# DDS.net
KiCad netlist of a schematic drawn in Altium Designer
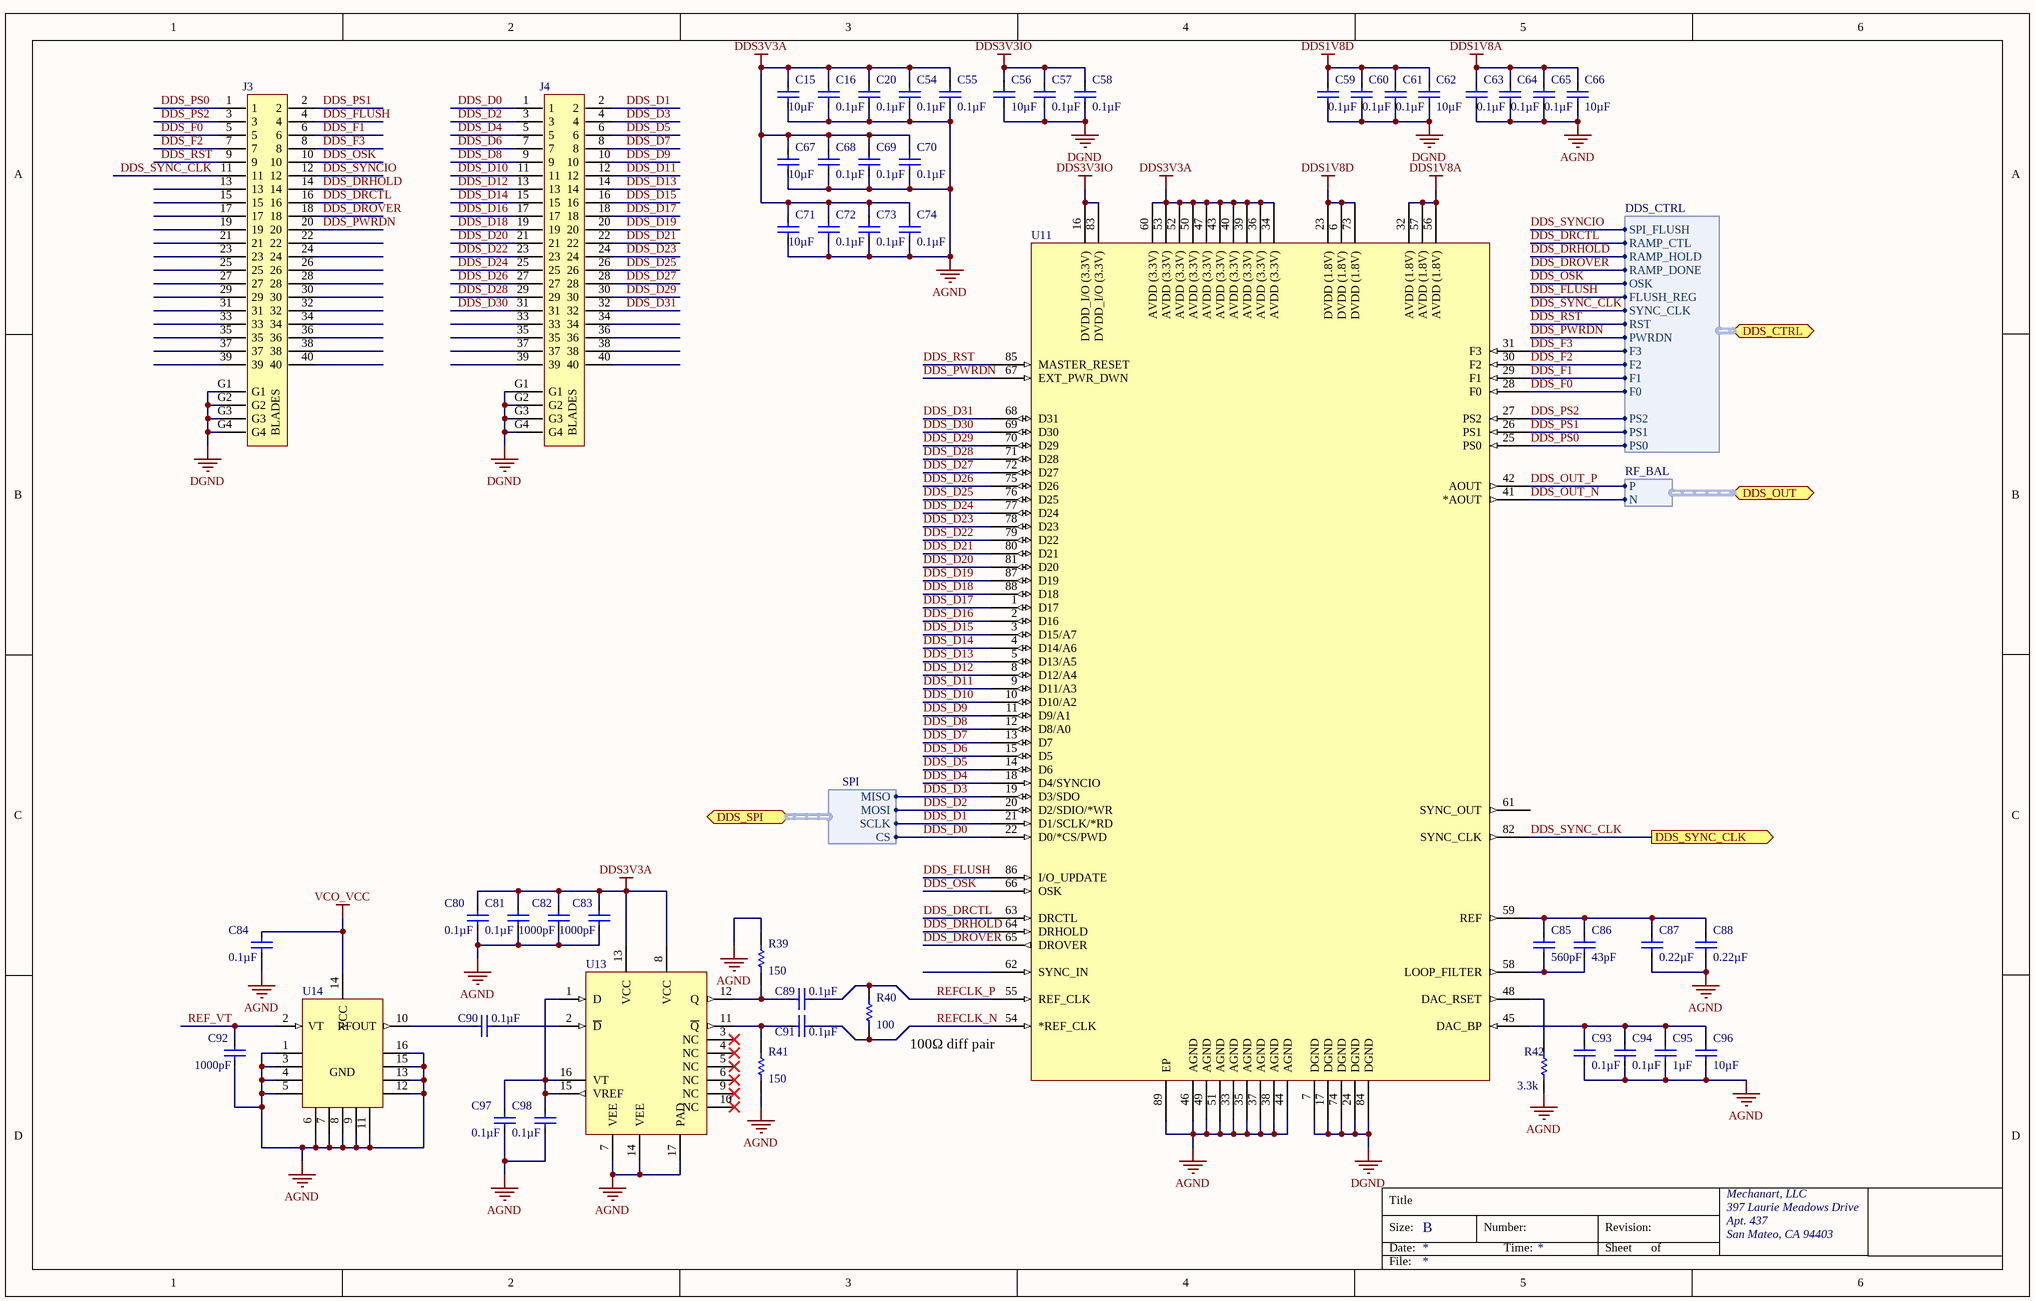
[diagram p0: DDS.SchDoc]

(export (version "E")
  (design (tool "Eeschema 10.0.6"))
  (components
    (comp (ref "C15")
      (value "10µF")
      (footprint "CAPC1608X85L22N")
      (description "CAP CER 10UF 25V X7R 1206")
      (fields
        (field (name "MANUFACTURER") "Murata Electronics North America")
        (field (name "MANUFACTURER PART NUMBER") "GRM31CR71E106KA12L")
      )
      (libsource (lib "mechanart_oshw") (part "CapSMT"))
    )
    (comp (ref "C16")
      (value "0.1µF")
      (footprint "CAPC1005X55L25N")
      (description "CAP CER 0.1UF 16V X7R 0402")
      (fields
        (field (name "MANUFACTURER") "Murata Electronics North America")
        (field (name "MANUFACTURER PART NUMBER") "GRM155R71C104JA88D")
      )
      (libsource (lib "mechanart_oshw") (part "CapSMT"))
    )
    (comp (ref "C20")
      (value "0.1µF")
      (footprint "CAPC1005X55L25N")
      (description "CAP CER 0.1UF 16V X7R 0402")
      (fields
        (field (name "MANUFACTURER") "Murata Electronics North America")
        (field (name "MANUFACTURER PART NUMBER") "GRM155R71C104JA88D")
      )
      (libsource (lib "mechanart_oshw") (part "CapSMT"))
    )
    (comp (ref "C54")
      (value "0.1µF")
      (footprint "CAPC1005X55L25N")
      (description "CAP CER 0.1UF 16V X7R 0402")
      (fields
        (field (name "MANUFACTURER") "Murata Electronics North America")
        (field (name "MANUFACTURER PART NUMBER") "GRM155R71C104JA88D")
      )
      (libsource (lib "mechanart_oshw") (part "CapSMT"))
    )
    (comp (ref "C55")
      (value "0.1µF")
      (footprint "CAPC1005X55L25N")
      (description "CAP CER 0.1UF 16V X7R 0402")
      (fields
        (field (name "MANUFACTURER") "Murata Electronics North America")
        (field (name "MANUFACTURER PART NUMBER") "GRM155R71C104JA88D")
      )
      (libsource (lib "mechanart_oshw") (part "CapSMT"))
    )
    (comp (ref "C56")
      (value "10µF")
      (footprint "CAPC1608X85L22N")
      (description "CAP CER 10UF 25V X7R 1206")
      (fields
        (field (name "MANUFACTURER") "Murata Electronics North America")
        (field (name "MANUFACTURER PART NUMBER") "GRM31CR71E106KA12L")
      )
      (libsource (lib "mechanart_oshw") (part "CapSMT"))
    )
    (comp (ref "C57")
      (value "0.1µF")
      (footprint "CAPC1005X55L25N")
      (description "CAP CER 0.1UF 16V X7R 0402")
      (fields
        (field (name "MANUFACTURER") "Murata Electronics North America")
        (field (name "MANUFACTURER PART NUMBER") "GRM155R71C104JA88D")
      )
      (libsource (lib "mechanart_oshw") (part "CapSMT"))
    )
    (comp (ref "C58")
      (value "0.1µF")
      (footprint "CAPC1005X55L25N")
      (description "CAP CER 0.1UF 16V X7R 0402")
      (fields
        (field (name "MANUFACTURER") "Murata Electronics North America")
        (field (name "MANUFACTURER PART NUMBER") "GRM155R71C104JA88D")
      )
      (libsource (lib "mechanart_oshw") (part "CapSMT"))
    )
    (comp (ref "C59")
      (value "0.1µF")
      (footprint "CAPC1005X55L25N")
      (description "CAP CER 0.1UF 16V X7R 0402")
      (fields
        (field (name "MANUFACTURER") "Murata Electronics North America")
        (field (name "MANUFACTURER PART NUMBER") "GRM155R71C104JA88D")
      )
      (libsource (lib "mechanart_oshw") (part "CapSMT"))
    )
    (comp (ref "C60")
      (value "0.1µF")
      (footprint "CAPC1005X55L25N")
      (description "CAP CER 0.1UF 16V X7R 0402")
      (fields
        (field (name "MANUFACTURER") "Murata Electronics North America")
        (field (name "MANUFACTURER PART NUMBER") "GRM155R71C104JA88D")
      )
      (libsource (lib "mechanart_oshw") (part "CapSMT"))
    )
    (comp (ref "C61")
      (value "0.1µF")
      (footprint "CAPC1005X55L25N")
      (description "CAP CER 0.1UF 16V X7R 0402")
      (fields
        (field (name "MANUFACTURER") "Murata Electronics North America")
        (field (name "MANUFACTURER PART NUMBER") "GRM155R71C104JA88D")
      )
      (libsource (lib "mechanart_oshw") (part "CapSMT"))
    )
    (comp (ref "C62")
      (value "10µF")
      (footprint "CAPC1608X85L22N")
      (description "CAP CER 10UF 25V X7R 1206")
      (fields
        (field (name "MANUFACTURER") "Murata Electronics North America")
        (field (name "MANUFACTURER PART NUMBER") "GRM31CR71E106KA12L")
      )
      (libsource (lib "mechanart_oshw") (part "CapSMT"))
    )
    (comp (ref "C63")
      (value "0.1µF")
      (footprint "CAPC1005X55L25N")
      (description "CAP CER 0.1UF 16V X7R 0402")
      (fields
        (field (name "MANUFACTURER") "Murata Electronics North America")
        (field (name "MANUFACTURER PART NUMBER") "GRM155R71C104JA88D")
      )
      (libsource (lib "mechanart_oshw") (part "CapSMT"))
    )
    (comp (ref "C64")
      (value "0.1µF")
      (footprint "CAPC1005X55L25N")
      (description "CAP CER 0.1UF 16V X7R 0402")
      (fields
        (field (name "MANUFACTURER") "Murata Electronics North America")
        (field (name "MANUFACTURER PART NUMBER") "GRM155R71C104JA88D")
      )
      (libsource (lib "mechanart_oshw") (part "CapSMT"))
    )
    (comp (ref "C65")
      (value "0.1µF")
      (footprint "CAPC1005X55L25N")
      (description "CAP CER 0.1UF 16V X7R 0402")
      (fields
        (field (name "MANUFACTURER") "Murata Electronics North America")
        (field (name "MANUFACTURER PART NUMBER") "GRM155R71C104JA88D")
      )
      (libsource (lib "mechanart_oshw") (part "CapSMT"))
    )
    (comp (ref "C66")
      (value "10µF")
      (footprint "CAPC1608X85L22N")
      (description "CAP CER 10UF 25V X7R 1206")
      (fields
        (field (name "MANUFACTURER") "Murata Electronics North America")
        (field (name "MANUFACTURER PART NUMBER") "GRM31CR71E106KA12L")
      )
      (libsource (lib "mechanart_oshw") (part "CapSMT"))
    )
    (comp (ref "C67")
      (value "10µF")
      (footprint "CAPC1608X85L22N")
      (description "CAP CER 10UF 25V X7R 1206")
      (fields
        (field (name "MANUFACTURER") "Murata Electronics North America")
        (field (name "MANUFACTURER PART NUMBER") "GRM31CR71E106KA12L")
      )
      (libsource (lib "mechanart_oshw") (part "CapSMT"))
    )
    (comp (ref "C68")
      (value "0.1µF")
      (footprint "CAPC1005X55L25N")
      (description "CAP CER 0.1UF 16V X7R 0402")
      (fields
        (field (name "MANUFACTURER") "Murata Electronics North America")
        (field (name "MANUFACTURER PART NUMBER") "GRM155R71C104JA88D")
      )
      (libsource (lib "mechanart_oshw") (part "CapSMT"))
    )
    (comp (ref "C69")
      (value "0.1µF")
      (footprint "CAPC1005X55L25N")
      (description "CAP CER 0.1UF 16V X7R 0402")
      (fields
        (field (name "MANUFACTURER") "Murata Electronics North America")
        (field (name "MANUFACTURER PART NUMBER") "GRM155R71C104JA88D")
      )
      (libsource (lib "mechanart_oshw") (part "CapSMT"))
    )
    (comp (ref "C70")
      (value "0.1µF")
      (footprint "CAPC1005X55L25N")
      (description "CAP CER 0.1UF 16V X7R 0402")
      (fields
        (field (name "MANUFACTURER") "Murata Electronics North America")
        (field (name "MANUFACTURER PART NUMBER") "GRM155R71C104JA88D")
      )
      (libsource (lib "mechanart_oshw") (part "CapSMT"))
    )
    (comp (ref "C71")
      (value "10µF")
      (footprint "CAPC1608X85L22N")
      (description "CAP CER 10UF 25V X7R 1206")
      (fields
        (field (name "MANUFACTURER") "Murata Electronics North America")
        (field (name "MANUFACTURER PART NUMBER") "GRM31CR71E106KA12L")
      )
      (libsource (lib "mechanart_oshw") (part "CapSMT"))
    )
    (comp (ref "C72")
      (value "0.1µF")
      (footprint "CAPC1005X55L25N")
      (description "CAP CER 0.1UF 16V X7R 0402")
      (fields
        (field (name "MANUFACTURER") "Murata Electronics North America")
        (field (name "MANUFACTURER PART NUMBER") "GRM155R71C104JA88D")
      )
      (libsource (lib "mechanart_oshw") (part "CapSMT"))
    )
    (comp (ref "C73")
      (value "0.1µF")
      (footprint "CAPC1005X55L25N")
      (description "CAP CER 0.1UF 16V X7R 0402")
      (fields
        (field (name "MANUFACTURER") "Murata Electronics North America")
        (field (name "MANUFACTURER PART NUMBER") "GRM155R71C104JA88D")
      )
      (libsource (lib "mechanart_oshw") (part "CapSMT"))
    )
    (comp (ref "C74")
      (value "0.1µF")
      (footprint "CAPC1005X55L25N")
      (description "CAP CER 0.1UF 16V X7R 0402")
      (fields
        (field (name "MANUFACTURER") "Murata Electronics North America")
        (field (name "MANUFACTURER PART NUMBER") "GRM155R71C104JA88D")
      )
      (libsource (lib "mechanart_oshw") (part "CapSMT"))
    )
    (comp (ref "C80")
      (value "0.1µF")
      (footprint "CAPC1005X50L25N")
      (description "CAP CER 0.1UF 50V X7R 0402")
      (fields
        (field (name "MANUFACTURER") "Murata Electronics North America")
        (field (name "MANUFACTURER PART NUMBER") "GRM155R71H104KE14D")
      )
      (libsource (lib "mechanart_oshw") (part "CapSMT"))
    )
    (comp (ref "C81")
      (value "0.1µF")
      (footprint "CAPC1005X50L25N")
      (description "CAP CER 0.1UF 50V X7R 0402")
      (fields
        (field (name "MANUFACTURER") "Murata Electronics North America")
        (field (name "MANUFACTURER PART NUMBER") "GRM155R71H104KE14D")
      )
      (libsource (lib "mechanart_oshw") (part "CapSMT"))
    )
    (comp (ref "C82")
      (value "1000pF")
      (footprint "CAPC1005X50L25N")
      (description "CAP CER 1000PF 50V NP0 0402")
      (fields
        (field (name "MANUFACTURER") "Murata Electronics North America")
        (field (name "MANUFACTURER PART NUMBER") "GRM1555C1H102JA01D")
      )
      (libsource (lib "mechanart_oshw") (part "CapSMT"))
    )
    (comp (ref "C83")
      (value "1000pF")
      (footprint "CAPC1005X50L25N")
      (description "CAP CER 1000PF 50V NP0 0402")
      (fields
        (field (name "MANUFACTURER") "Murata Electronics North America")
        (field (name "MANUFACTURER PART NUMBER") "GRM1555C1H102JA01D")
      )
      (libsource (lib "mechanart_oshw") (part "CapSMT"))
    )
    (comp (ref "C84")
      (value "0.1µF")
      (footprint "CAPC1005X50L25N")
      (description "CAP CER 0.1UF 50V X7R 0402")
      (fields
        (field (name "MANUFACTURER") "Murata Electronics North America")
        (field (name "MANUFACTURER PART NUMBER") "GRM155R71H104KE14D")
      )
      (libsource (lib "mechanart_oshw") (part "CapSMT"))
    )
    (comp (ref "C85")
      (value "560pF")
      (footprint "CAPC1005X50L25N")
      (description "CAP CER 560PF 50V NP0 0402")
      (fields
        (field (name "MANUFACTURER") "Murata Electronics North America")
        (field (name "MANUFACTURER PART NUMBER") "GRM1555C1H561JA01D")
      )
      (libsource (lib "mechanart_oshw") (part "CapSMT"))
    )
    (comp (ref "C86")
      (value "43pF")
      (footprint "CAPC1005X50L25N")
      (description "CAP CER 43PF 50V NP0 0402")
      (fields
        (field (name "MANUFACTURER") "Murata Electronics North America")
        (field (name "MANUFACTURER PART NUMBER") "GRM1555C1H430JA01D")
      )
      (libsource (lib "mechanart_oshw") (part "CapSMT"))
    )
    (comp (ref "C87")
      (value "0.22µF")
      (footprint "CAPC1005X50L25N")
      (description "CAP CER 0.22UF 35V 10% X5R 0402")
      (fields
        (field (name "MANUFACTURER") "Murata Electronics North America")
        (field (name "MANUFACTURER PART NUMBER") "GRT155R6YA224KE01D")
      )
      (libsource (lib "mechanart_oshw") (part "CapSMT"))
    )
    (comp (ref "C88")
      (value "0.22µF")
      (footprint "CAPC1005X50L25N")
      (description "CAP CER 0.22UF 35V 10% X5R 0402")
      (fields
        (field (name "MANUFACTURER") "Murata Electronics North America")
        (field (name "MANUFACTURER PART NUMBER") "GRT155R6YA224KE01D")
      )
      (libsource (lib "mechanart_oshw") (part "CapSMT"))
    )
    (comp (ref "C89")
      (value "0.1µF")
      (footprint "CAPC1005X55L25N")
      (description "CAP CER 0.1UF 16V X7R 0402")
      (fields
        (field (name "MANUFACTURER") "Murata Electronics North America")
        (field (name "MANUFACTURER PART NUMBER") "GRM155R71C104JA88D")
      )
      (libsource (lib "mechanart_oshw") (part "CapSMT"))
    )
    (comp (ref "C90")
      (value "0.1µF")
      (footprint "CAPC1005X55L25N")
      (description "CAP CER 0.1UF 16V X7R 0402")
      (fields
        (field (name "MANUFACTURER") "Murata Electronics North America")
        (field (name "MANUFACTURER PART NUMBER") "GRM155R71C104JA88D")
      )
      (libsource (lib "mechanart_oshw") (part "CapSMT"))
    )
    (comp (ref "C91")
      (value "0.1µF")
      (footprint "CAPC1005X55L25N")
      (description "CAP CER 0.1UF 16V X7R 0402")
      (fields
        (field (name "MANUFACTURER") "Murata Electronics North America")
        (field (name "MANUFACTURER PART NUMBER") "GRM155R71C104JA88D")
      )
      (libsource (lib "mechanart_oshw") (part "CapSMT"))
    )
    (comp (ref "C92")
      (value "1000pF")
      (footprint "CAPC1005X50L25N")
      (description "CAP CER 1000PF 50V NP0 0402")
      (fields
        (field (name "MANUFACTURER") "Murata Electronics North America")
        (field (name "MANUFACTURER PART NUMBER") "GRM1555C1H102JA01D")
      )
      (libsource (lib "mechanart_oshw") (part "CapSMT"))
    )
    (comp (ref "C93")
      (value "0.1µF")
      (footprint "CAPC1005X55L25N")
      (description "CAP CER 0.1UF 16V X7R 0402")
      (fields
        (field (name "MANUFACTURER") "Murata Electronics North America")
        (field (name "MANUFACTURER PART NUMBER") "GRM155R71C104JA88D")
      )
      (libsource (lib "mechanart_oshw") (part "CapSMT"))
    )
    (comp (ref "C94")
      (value "0.1µF")
      (footprint "CAPC1005X55L25N")
      (description "CAP CER 0.1UF 16V X7R 0402")
      (fields
        (field (name "MANUFACTURER") "Murata Electronics North America")
        (field (name "MANUFACTURER PART NUMBER") "GRM155R71C104JA88D")
      )
      (libsource (lib "mechanart_oshw") (part "CapSMT"))
    )
    (comp (ref "C95")
      (value "1µF")
      (footprint "CAPC1608X85L22N")
      (description "CAP CER 1UF 16V X7R 0603")
      (fields
        (field (name "MANUFACTURER") "Taiyo Yuden")
        (field (name "MANUFACTURER PART NUMBER") "EMK107B7105KA-T")
      )
      (libsource (lib "mechanart_oshw") (part "CapSMT"))
    )
    (comp (ref "C96")
      (value "10µF")
      (footprint "CAPC1608X85L22N")
      (description "CAP CER 10UF 25V X7R 1206")
      (fields
        (field (name "MANUFACTURER") "Murata Electronics North America")
        (field (name "MANUFACTURER PART NUMBER") "GRM31CR71E106KA12L")
      )
      (libsource (lib "mechanart_oshw") (part "CapSMT"))
    )
    (comp (ref "C97")
      (value "0.1µF")
      (footprint "CAPC1005X50L25N")
      (description "CAP CER 0.1UF 50V X7R 0402")
      (fields
        (field (name "MANUFACTURER") "Murata Electronics North America")
        (field (name "MANUFACTURER PART NUMBER") "GRM155R71H104KE14D")
      )
      (libsource (lib "mechanart_oshw") (part "CapSMT"))
    )
    (comp (ref "C98")
      (value "0.1µF")
      (footprint "CAPC1005X50L25N")
      (description "CAP CER 0.1UF 50V X7R 0402")
      (fields
        (field (name "MANUFACTURER") "Murata Electronics North America")
        (field (name "MANUFACTURER PART NUMBER") "GRM155R71H104KE14D")
      )
      (libsource (lib "mechanart_oshw") (part "CapSMT"))
    )
    (comp (ref "J3")
      (value "QSE-020-01-X-D-A")
      (footprint "QSE-020-01-X-D-A")
      (description "CONN RCPT HI-SPEED DUAL 40POS")
      (fields
        (field (name "MANUFACTURER") "Samtec Inc.")
        (field (name "MANUFACTURER PART NUMBER") "QSE-020-01-L-D-A")
      )
      (libsource (lib "mechanart_oshw") (part "QSE-020-01-X-D-A"))
    )
    (comp (ref "J4")
      (value "QSE-020-01-X-D-A")
      (footprint "QSE-020-01-X-D-A")
      (description "CONN RCPT HI-SPEED DUAL 40POS")
      (fields
        (field (name "MANUFACTURER") "Samtec Inc.")
        (field (name "MANUFACTURER PART NUMBER") "QSE-020-01-L-D-A")
      )
      (libsource (lib "mechanart_oshw") (part "QSE-020-01-X-D-A"))
    )
    (comp (ref "R39")
      (value "150")
      (footprint "RESC1005X40L25N")
      (description "RES SMD 150 OHM 1% 1/10W 0402")
      (fields
        (field (name "MANUFACTURER") "Panasonic Electronic Components")
        (field (name "MANUFACTURER PART NUMBER") "ERJ-2RKF1500X")
      )
      (libsource (lib "mechanart_oshw") (part "ResSMT"))
    )
    (comp (ref "R40")
      (value "100")
      (footprint "RESC1005X40L25N")
      (description "RES SMD 100 OHM 1% 1/10W 0402")
      (fields
        (field (name "MANUFACTURER") "Panasonic Electronic Components")
        (field (name "MANUFACTURER PART NUMBER") "ERJ-2RKF1000X")
      )
      (libsource (lib "mechanart_oshw") (part "ResSMT"))
    )
    (comp (ref "R41")
      (value "150")
      (footprint "RESC1005X40L25N")
      (description "RES SMD 150 OHM 1% 1/10W 0402")
      (fields
        (field (name "MANUFACTURER") "Panasonic Electronic Components")
        (field (name "MANUFACTURER PART NUMBER") "ERJ-2RKF1500X")
      )
      (libsource (lib "mechanart_oshw") (part "ResSMT"))
    )
    (comp (ref "R42")
      (value "3.3k")
      (footprint "RESC1005X40L25N")
      (description "RES SMD 3.3K OHM 1% 1/10W 0402")
      (fields
        (field (name "MANUFACTURER") "Panasonic Electronic Components")
        (field (name "MANUFACTURER PART NUMBER") "ERJ-2RKF3301X")
      )
      (libsource (lib "mechanart_oshw") (part "ResSMT"))
    )
    (comp (ref "U11")
      (value "AD9914BCPZ")
      (footprint "QFN50P1200X1200X90-89T670X670N")
      (description "IC DDS 3.5GSPS DAC 12BIT 88LFCSP")
      (fields (field (name "MANUFACTURER") "Analog Devices Inc"))
      (libsource (lib "mechanart_oshw") (part "AD9914BCPZ"))
    )
    (comp (ref "U13")
      (value "ADCLK905")
      (footprint "QFN50P300X300X90-17T150X150N")
      (description "IC CLK BUFFER 1:1 7.5GHZ 16LFCSP")
      (fields
        (field (name "MANUFACTURER") "Analog Devices Inc.")
        (field (name "MANUFACTURER PART NUMBER") "ADCLK905BCPZ-R7")
      )
      (libsource (lib "mechanart_oshw") (part "ADCLK905"))
    )
    (comp (ref "U14")
      (value "CVCO55")
      (footprint "CVCO55")
      (description "OSC CRO 3500-3700 MHZ SMD .5X.5\"")
      (fields
        (field (name "MANUFACTURER") "Crystek Corporation")
        (field (name "MANUFACTURER PART NUMBER") "CVCO55CC-3500-3700")
      )
      (libsource (lib "mechanart_oshw") (part "CVCO55"))
    )
  )
  (nets
    (net (code "4") (name "/DDS_D0") (class "Default")
      (node (ref "J4") (pin "1") (pinfunction "1_1") (pintype "passive"))
      (node (ref "U11") (pin "22") (pinfunction "D0/*CS/PWD_22") (pintype "input"))
    )
    (net (code "5") (name "/DDS_D1") (class "Default")
      (node (ref "J4") (pin "2") (pinfunction "2_2") (pintype "passive"))
      (node (ref "U11") (pin "21") (pinfunction "D1/SCLK/*RD_21") (pintype "input"))
    )
    (net (code "6") (name "/DDS_D2") (class "Default")
      (node (ref "J4") (pin "3") (pinfunction "3_3") (pintype "passive"))
      (node (ref "U11") (pin "20") (pinfunction "D2/SDIO/*WR_20") (pintype "bidirectional"))
    )
    (net (code "7") (name "/DDS_D3") (class "Default")
      (node (ref "J4") (pin "4") (pinfunction "4_4") (pintype "passive"))
      (node (ref "U11") (pin "19") (pinfunction "D3/SDO_19") (pintype "bidirectional"))
    )
    (net (code "8") (name "/DDS_D4") (class "Default")
      (node (ref "J4") (pin "5") (pinfunction "5_5") (pintype "passive"))
      (node (ref "U11") (pin "18") (pinfunction "D4/SYNCIO_18") (pintype "input"))
    )
    (net (code "9") (name "/DDS_D5") (class "Default")
      (node (ref "J4") (pin "6") (pinfunction "6_6") (pintype "passive"))
      (node (ref "U11") (pin "14") (pinfunction "D6_14") (pintype "bidirectional"))
    )
    (net (code "10") (name "/DDS_D6") (class "Default")
      (node (ref "J4") (pin "7") (pinfunction "7_7") (pintype "passive"))
      (node (ref "U11") (pin "15") (pinfunction "D5_15") (pintype "bidirectional"))
    )
    (net (code "11") (name "/DDS_D7") (class "Default")
      (node (ref "J4") (pin "8") (pinfunction "8_8") (pintype "passive"))
      (node (ref "U11") (pin "13") (pinfunction "D7_13") (pintype "bidirectional"))
    )
    (net (code "12") (name "/DDS_D8") (class "Default")
      (node (ref "J4") (pin "9") (pinfunction "9_9") (pintype "passive"))
      (node (ref "U11") (pin "12") (pinfunction "D8/A0_12") (pintype "bidirectional"))
    )
    (net (code "13") (name "/DDS_D9") (class "Default")
      (node (ref "J4") (pin "10") (pinfunction "10_10") (pintype "passive"))
      (node (ref "U11") (pin "11") (pinfunction "D9/A1_11") (pintype "bidirectional"))
    )
    (net (code "14") (name "/DDS_D10") (class "Default")
      (node (ref "J4") (pin "11") (pinfunction "11_11") (pintype "passive"))
      (node (ref "U11") (pin "10") (pinfunction "D10/A2_10") (pintype "bidirectional"))
    )
    (net (code "15") (name "/DDS_D11") (class "Default")
      (node (ref "J4") (pin "12") (pinfunction "12_12") (pintype "passive"))
      (node (ref "U11") (pin "9") (pinfunction "D11/A3_9") (pintype "bidirectional"))
    )
    (net (code "16") (name "/DDS_D12") (class "Default")
      (node (ref "J4") (pin "13") (pinfunction "13_13") (pintype "passive"))
      (node (ref "U11") (pin "8") (pinfunction "D12/A4_8") (pintype "bidirectional"))
    )
    (net (code "17") (name "/DDS_D13") (class "Default")
      (node (ref "J4") (pin "14") (pinfunction "14_14") (pintype "passive"))
      (node (ref "U11") (pin "5") (pinfunction "D13/A5_5") (pintype "bidirectional"))
    )
    (net (code "18") (name "/DDS_D14") (class "Default")
      (node (ref "J4") (pin "15") (pinfunction "15_15") (pintype "passive"))
      (node (ref "U11") (pin "4") (pinfunction "D14/A6_4") (pintype "bidirectional"))
    )
    (net (code "19") (name "/DDS_D15") (class "Default")
      (node (ref "J4") (pin "16") (pinfunction "16_16") (pintype "passive"))
      (node (ref "U11") (pin "3") (pinfunction "D15/A7_3") (pintype "bidirectional"))
    )
    (net (code "20") (name "/DDS_D16") (class "Default")
      (node (ref "J4") (pin "17") (pinfunction "17_17") (pintype "passive"))
      (node (ref "U11") (pin "2") (pinfunction "D16_2") (pintype "bidirectional"))
    )
    (net (code "21") (name "/DDS_D17") (class "Default")
      (node (ref "J4") (pin "18") (pinfunction "18_18") (pintype "passive"))
      (node (ref "U11") (pin "1") (pinfunction "D17_1") (pintype "bidirectional"))
    )
    (net (code "22") (name "/DDS_D18") (class "Default")
      (node (ref "J4") (pin "19") (pinfunction "19_19") (pintype "passive"))
      (node (ref "U11") (pin "88") (pinfunction "D18_88") (pintype "bidirectional"))
    )
    (net (code "23") (name "/DDS_D19") (class "Default")
      (node (ref "J4") (pin "20") (pinfunction "20_20") (pintype "passive"))
      (node (ref "U11") (pin "87") (pinfunction "D19_87") (pintype "bidirectional"))
    )
    (net (code "24") (name "/DDS_D20") (class "Default")
      (node (ref "J4") (pin "21") (pinfunction "21_21") (pintype "passive"))
      (node (ref "U11") (pin "81") (pinfunction "D20_81") (pintype "bidirectional"))
    )
    (net (code "25") (name "/DDS_D21") (class "Default")
      (node (ref "J4") (pin "22") (pinfunction "22_22") (pintype "passive"))
      (node (ref "U11") (pin "80") (pinfunction "D21_80") (pintype "bidirectional"))
    )
    (net (code "26") (name "/DDS_D22") (class "Default")
      (node (ref "J4") (pin "23") (pinfunction "23_23") (pintype "passive"))
      (node (ref "U11") (pin "79") (pinfunction "D22_79") (pintype "bidirectional"))
    )
    (net (code "27") (name "/DDS_D23") (class "Default")
      (node (ref "J4") (pin "24") (pinfunction "24_24") (pintype "passive"))
      (node (ref "U11") (pin "78") (pinfunction "D23_78") (pintype "bidirectional"))
    )
    (net (code "28") (name "/DDS_D24") (class "Default")
      (node (ref "J4") (pin "25") (pinfunction "25_25") (pintype "passive"))
      (node (ref "U11") (pin "77") (pinfunction "D24_77") (pintype "bidirectional"))
    )
    (net (code "29") (name "/DDS_D25") (class "Default")
      (node (ref "J4") (pin "26") (pinfunction "26_26") (pintype "passive"))
      (node (ref "U11") (pin "76") (pinfunction "D25_76") (pintype "bidirectional"))
    )
    (net (code "30") (name "/DDS_D26") (class "Default")
      (node (ref "J4") (pin "27") (pinfunction "27_27") (pintype "passive"))
      (node (ref "U11") (pin "75") (pinfunction "D26_75") (pintype "bidirectional"))
    )
    (net (code "31") (name "/DDS_D27") (class "Default")
      (node (ref "J4") (pin "28") (pinfunction "28_28") (pintype "passive"))
      (node (ref "U11") (pin "72") (pinfunction "D27_72") (pintype "bidirectional"))
    )
    (net (code "32") (name "/DDS_D28") (class "Default")
      (node (ref "J4") (pin "29") (pinfunction "29_29") (pintype "passive"))
      (node (ref "U11") (pin "71") (pinfunction "D28_71") (pintype "bidirectional"))
    )
    (net (code "33") (name "/DDS_D29") (class "Default")
      (node (ref "J4") (pin "30") (pinfunction "30_30") (pintype "passive"))
      (node (ref "U11") (pin "70") (pinfunction "D29_70") (pintype "bidirectional"))
    )
    (net (code "34") (name "/DDS_D30") (class "Default")
      (node (ref "J4") (pin "31") (pinfunction "31_31") (pintype "passive"))
      (node (ref "U11") (pin "69") (pinfunction "D30_69") (pintype "bidirectional"))
    )
    (net (code "35") (name "/DDS_D31") (class "Default")
      (node (ref "J4") (pin "32") (pinfunction "32_32") (pintype "passive"))
      (node (ref "U11") (pin "68") (pinfunction "D31_68") (pintype "bidirectional"))
    )
    (net (code "36") (name "/DDS_DRCTL") (class "Default")
      (node (ref "J3") (pin "16") (pinfunction "16_16") (pintype "passive"))
      (node (ref "U11") (pin "63") (pinfunction "DRCTL_63") (pintype "input"))
    )
    (net (code "37") (name "/DDS_DRHOLD") (class "Default")
      (node (ref "J3") (pin "14") (pinfunction "14_14") (pintype "passive"))
      (node (ref "U11") (pin "64") (pinfunction "DRHOLD_64") (pintype "input"))
    )
    (net (code "38") (name "/DDS_DROVER") (class "Default")
      (node (ref "J3") (pin "18") (pinfunction "18_18") (pintype "passive"))
      (node (ref "U11") (pin "65") (pinfunction "DROVER_65") (pintype "output"))
    )
    (net (code "39") (name "/DDS_F0") (class "Default")
      (node (ref "J3") (pin "5") (pinfunction "5_5") (pintype "passive"))
      (node (ref "U11") (pin "28") (pinfunction "F0_28") (pintype "input"))
    )
    (net (code "40") (name "/DDS_F1") (class "Default")
      (node (ref "J3") (pin "6") (pinfunction "6_6") (pintype "passive"))
      (node (ref "U11") (pin "29") (pinfunction "F1_29") (pintype "input"))
    )
    (net (code "41") (name "/DDS_F2") (class "Default")
      (node (ref "J3") (pin "7") (pinfunction "7_7") (pintype "passive"))
      (node (ref "U11") (pin "30") (pinfunction "F2_30") (pintype "input"))
    )
    (net (code "42") (name "/DDS_F3") (class "Default")
      (node (ref "J3") (pin "8") (pinfunction "8_8") (pintype "passive"))
      (node (ref "U11") (pin "31") (pinfunction "F3_31") (pintype "input"))
    )
    (net (code "43") (name "/DDS_FLUSH") (class "Default")
      (node (ref "J3") (pin "4") (pinfunction "4_4") (pintype "passive"))
      (node (ref "U11") (pin "86") (pinfunction "I/O_UPDATE_86") (pintype "input"))
    )
    (net (code "44") (name "/DDS_OSK") (class "Default")
      (node (ref "J3") (pin "10") (pinfunction "10_10") (pintype "passive"))
      (node (ref "U11") (pin "66") (pinfunction "OSK_66") (pintype "input"))
    )
    (net (code "45") (name "/DDS_OUT_N") (class "Default")
      (node (ref "U11") (pin "41") (pinfunction "*AOUT_41") (pintype "output"))
    )
    (net (code "46") (name "/DDS_OUT_P") (class "Default")
      (node (ref "U11") (pin "42") (pinfunction "AOUT_42") (pintype "output"))
    )
    (net (code "47") (name "/DDS_PS0") (class "Default")
      (node (ref "J3") (pin "1") (pinfunction "1_1") (pintype "passive"))
      (node (ref "U11") (pin "25") (pinfunction "PS0_25") (pintype "input"))
    )
    (net (code "48") (name "/DDS_PS1") (class "Default")
      (node (ref "J3") (pin "2") (pinfunction "2_2") (pintype "passive"))
      (node (ref "U11") (pin "26") (pinfunction "PS1_26") (pintype "input"))
    )
    (net (code "49") (name "/DDS_PS2") (class "Default")
      (node (ref "J3") (pin "3") (pinfunction "3_3") (pintype "passive"))
      (node (ref "U11") (pin "27") (pinfunction "PS2_27") (pintype "input"))
    )
    (net (code "50") (name "/DDS_PWRDN") (class "Default")
      (node (ref "J3") (pin "20") (pinfunction "20_20") (pintype "passive"))
      (node (ref "U11") (pin "67") (pinfunction "EXT_PWR_DWN_67") (pintype "input"))
    )
    (net (code "51") (name "/DDS_RST") (class "Default")
      (node (ref "J3") (pin "9") (pinfunction "9_9") (pintype "passive"))
      (node (ref "U11") (pin "85") (pinfunction "MASTER_RESET_85") (pintype "input"))
    )
    (net (code "52") (name "/DDS_SYNCIO") (class "Default")
      (node (ref "J3") (pin "12") (pinfunction "12_12") (pintype "passive"))
    )
    (net (code "53") (name "/DDS_SYNC_CLK") (class "Default")
      (node (ref "J3") (pin "11") (pinfunction "11_11") (pintype "passive"))
      (node (ref "U11") (pin "82") (pinfunction "SYNC_CLK_82") (pintype "output"))
    )
    (net (code "54") (name "/REFCLK_N") (class "Default")
      (node (ref "C91") (pin "2") (pinfunction "2_2") (pintype "passive"))
      (node (ref "R40") (pin "1") (pinfunction "1_1") (pintype "passive"))
      (node (ref "U11") (pin "54") (pinfunction "*REF_CLK_54") (pintype "input"))
    )
    (net (code "55") (name "/REFCLK_P") (class "Default")
      (node (ref "C89") (pin "2") (pinfunction "2_2") (pintype "passive"))
      (node (ref "R40") (pin "2") (pinfunction "2_2") (pintype "passive"))
      (node (ref "U11") (pin "55") (pinfunction "REF_CLK_55") (pintype "input"))
    )
    (net (code "56") (name "/REF_VT") (class "Default")
      (node (ref "C92") (pin "1") (pinfunction "1_1") (pintype "passive"))
      (node (ref "U14") (pin "2") (pinfunction "VT_2") (pintype "input"))
    )
    (net (code "60") (name "AGND") (class "Default")
      (node (ref "C15") (pin "2") (pinfunction "2_2") (pintype "passive"))
      (node (ref "C16") (pin "2") (pinfunction "2_2") (pintype "passive"))
      (node (ref "C20") (pin "2") (pinfunction "2_2") (pintype "passive"))
      (node (ref "C54") (pin "2") (pinfunction "2_2") (pintype "passive"))
      (node (ref "C55") (pin "2") (pinfunction "2_2") (pintype "passive"))
      (node (ref "C63") (pin "2") (pinfunction "2_2") (pintype "passive"))
      (node (ref "C64") (pin "2") (pinfunction "2_2") (pintype "passive"))
      (node (ref "C65") (pin "2") (pinfunction "2_2") (pintype "passive"))
      (node (ref "C66") (pin "2") (pinfunction "2_2") (pintype "passive"))
      (node (ref "C67") (pin "2") (pinfunction "2_2") (pintype "passive"))
      (node (ref "C68") (pin "2") (pinfunction "2_2") (pintype "passive"))
      (node (ref "C69") (pin "2") (pinfunction "2_2") (pintype "passive"))
      (node (ref "C70") (pin "2") (pinfunction "2_2") (pintype "passive"))
      (node (ref "C71") (pin "2") (pinfunction "2_2") (pintype "passive"))
      (node (ref "C72") (pin "2") (pinfunction "2_2") (pintype "passive"))
      (node (ref "C73") (pin "2") (pinfunction "2_2") (pintype "passive"))
      (node (ref "C74") (pin "2") (pinfunction "2_2") (pintype "passive"))
      (node (ref "C80") (pin "2") (pinfunction "2_2") (pintype "passive"))
      (node (ref "C81") (pin "2") (pinfunction "2_2") (pintype "passive"))
      (node (ref "C82") (pin "2") (pinfunction "2_2") (pintype "passive"))
      (node (ref "C83") (pin "2") (pinfunction "2_2") (pintype "passive"))
      (node (ref "C84") (pin "2") (pinfunction "2_2") (pintype "passive"))
      (node (ref "C87") (pin "2") (pinfunction "2_2") (pintype "passive"))
      (node (ref "C88") (pin "2") (pinfunction "2_2") (pintype "passive"))
      (node (ref "C92") (pin "2") (pinfunction "2_2") (pintype "passive"))
      (node (ref "C93") (pin "2") (pinfunction "2_2") (pintype "passive"))
      (node (ref "C94") (pin "2") (pinfunction "2_2") (pintype "passive"))
      (node (ref "C95") (pin "2") (pinfunction "2_2") (pintype "passive"))
      (node (ref "C96") (pin "2") (pinfunction "2_2") (pintype "passive"))
      (node (ref "C97") (pin "2") (pinfunction "2_2") (pintype "passive"))
      (node (ref "C98") (pin "2") (pinfunction "2_2") (pintype "passive"))
      (node (ref "R39") (pin "2") (pinfunction "2_2") (pintype "passive"))
      (node (ref "R41") (pin "1") (pinfunction "1_1") (pintype "passive"))
      (node (ref "R42") (pin "1") (pinfunction "1_1") (pintype "passive"))
      (node (ref "U11") (pin "33") (pinfunction "AGND_33") (pintype "power_in"))
      (node (ref "U11") (pin "35") (pinfunction "AGND_35") (pintype "power_in"))
      (node (ref "U11") (pin "37") (pinfunction "AGND_37") (pintype "power_in"))
      (node (ref "U11") (pin "38") (pinfunction "AGND_38") (pintype "power_in"))
      (node (ref "U11") (pin "44") (pinfunction "AGND_44") (pintype "power_in"))
      (node (ref "U11") (pin "46") (pinfunction "AGND_46") (pintype "power_in"))
      (node (ref "U11") (pin "49") (pinfunction "AGND_49") (pintype "power_in"))
      (node (ref "U11") (pin "51") (pinfunction "AGND_51") (pintype "power_in"))
      (node (ref "U11") (pin "89") (pinfunction "EP_89") (pintype "power_in"))
      (node (ref "U13") (pin "14") (pinfunction "VEE_14") (pintype "power_in"))
      (node (ref "U13") (pin "17") (pinfunction "PAD_17") (pintype "passive"))
      (node (ref "U13") (pin "7") (pinfunction "VEE_7") (pintype "power_in"))
      (node (ref "U14") (pin "1") (pinfunction "GND_1") (pintype "power_in"))
      (node (ref "U14") (pin "11") (pinfunction "GND_11") (pintype "power_in"))
      (node (ref "U14") (pin "12") (pinfunction "GND_12") (pintype "power_in"))
      (node (ref "U14") (pin "13") (pinfunction "GND_13") (pintype "power_in"))
      (node (ref "U14") (pin "15") (pinfunction "GND_15") (pintype "power_in"))
      (node (ref "U14") (pin "16") (pinfunction "GND_16") (pintype "power_in"))
      (node (ref "U14") (pin "3") (pinfunction "GND_3") (pintype "power_in"))
      (node (ref "U14") (pin "4") (pinfunction "GND_4") (pintype "power_in"))
      (node (ref "U14") (pin "5") (pinfunction "GND_5") (pintype "power_in"))
      (node (ref "U14") (pin "6") (pinfunction "GND_6") (pintype "power_in"))
      (node (ref "U14") (pin "7") (pinfunction "GND_7") (pintype "power_in"))
      (node (ref "U14") (pin "8") (pinfunction "GND_8") (pintype "power_in"))
      (node (ref "U14") (pin "9") (pinfunction "GND_9") (pintype "power_in"))
    )
    (net (code "61") (name "DDS1V8A") (class "Default")
      (node (ref "C63") (pin "1") (pinfunction "1_1") (pintype "passive"))
      (node (ref "C64") (pin "1") (pinfunction "1_1") (pintype "passive"))
      (node (ref "C65") (pin "1") (pinfunction "1_1") (pintype "passive"))
      (node (ref "C66") (pin "1") (pinfunction "1_1") (pintype "passive"))
      (node (ref "U11") (pin "32") (pinfunction "AVDD_(1.8V)_32") (pintype "power_in"))
      (node (ref "U11") (pin "56") (pinfunction "AVDD_(1.8V)_56") (pintype "power_in"))
      (node (ref "U11") (pin "57") (pinfunction "AVDD_(1.8V)_57") (pintype "power_in"))
    )
    (net (code "62") (name "DDS1V8D") (class "Default")
      (node (ref "C59") (pin "1") (pinfunction "1_1") (pintype "passive"))
      (node (ref "C60") (pin "1") (pinfunction "1_1") (pintype "passive"))
      (node (ref "C61") (pin "1") (pinfunction "1_1") (pintype "passive"))
      (node (ref "C62") (pin "1") (pinfunction "1_1") (pintype "passive"))
      (node (ref "U11") (pin "23") (pinfunction "DVDD_(1.8V)_23") (pintype "power_in"))
      (node (ref "U11") (pin "6") (pinfunction "DVDD_(1.8V)_6") (pintype "power_in"))
      (node (ref "U11") (pin "73") (pinfunction "DVDD_(1.8V)_73") (pintype "power_in"))
    )
    (net (code "63") (name "DDS3V3A") (class "Default")
      (node (ref "C15") (pin "1") (pinfunction "1_1") (pintype "passive"))
      (node (ref "C16") (pin "1") (pinfunction "1_1") (pintype "passive"))
      (node (ref "C20") (pin "1") (pinfunction "1_1") (pintype "passive"))
      (node (ref "C54") (pin "1") (pinfunction "1_1") (pintype "passive"))
      (node (ref "C55") (pin "1") (pinfunction "1_1") (pintype "passive"))
      (node (ref "C67") (pin "1") (pinfunction "1_1") (pintype "passive"))
      (node (ref "C68") (pin "1") (pinfunction "1_1") (pintype "passive"))
      (node (ref "C69") (pin "1") (pinfunction "1_1") (pintype "passive"))
      (node (ref "C70") (pin "1") (pinfunction "1_1") (pintype "passive"))
      (node (ref "C71") (pin "1") (pinfunction "1_1") (pintype "passive"))
      (node (ref "C72") (pin "1") (pinfunction "1_1") (pintype "passive"))
      (node (ref "C73") (pin "1") (pinfunction "1_1") (pintype "passive"))
      (node (ref "C74") (pin "1") (pinfunction "1_1") (pintype "passive"))
      (node (ref "C80") (pin "1") (pinfunction "1_1") (pintype "passive"))
      (node (ref "C81") (pin "1") (pinfunction "1_1") (pintype "passive"))
      (node (ref "C82") (pin "1") (pinfunction "1_1") (pintype "passive"))
      (node (ref "C83") (pin "1") (pinfunction "1_1") (pintype "passive"))
      (node (ref "U11") (pin "34") (pinfunction "AVDD_(3.3V)_34") (pintype "power_in"))
      (node (ref "U11") (pin "36") (pinfunction "AVDD_(3.3V)_36") (pintype "power_in"))
      (node (ref "U11") (pin "39") (pinfunction "AVDD_(3.3V)_39") (pintype "power_in"))
      (node (ref "U11") (pin "40") (pinfunction "AVDD_(3.3V)_40") (pintype "power_in"))
      (node (ref "U11") (pin "43") (pinfunction "AVDD_(3.3V)_43") (pintype "power_in"))
      (node (ref "U11") (pin "47") (pinfunction "AVDD_(3.3V)_47") (pintype "power_in"))
      (node (ref "U11") (pin "50") (pinfunction "AVDD_(3.3V)_50") (pintype "power_in"))
      (node (ref "U11") (pin "52") (pinfunction "AVDD_(3.3V)_52") (pintype "power_in"))
      (node (ref "U11") (pin "53") (pinfunction "AVDD_(3.3V)_53") (pintype "power_in"))
      (node (ref "U11") (pin "60") (pinfunction "AVDD_(3.3V)_60") (pintype "power_in"))
      (node (ref "U13") (pin "13") (pinfunction "VCC_13") (pintype "power_in"))
      (node (ref "U13") (pin "8") (pinfunction "VCC_8") (pintype "power_in"))
    )
    (net (code "64") (name "DDS3V3IO") (class "Default")
      (node (ref "C56") (pin "1") (pinfunction "1_1") (pintype "passive"))
      (node (ref "C57") (pin "1") (pinfunction "1_1") (pintype "passive"))
      (node (ref "C58") (pin "1") (pinfunction "1_1") (pintype "passive"))
      (node (ref "U11") (pin "16") (pinfunction "DVDD_I/O_(3.3V)_16") (pintype "power_in"))
      (node (ref "U11") (pin "83") (pinfunction "DVDD_I/O_(3.3V)_83") (pintype "power_in"))
    )
    (net (code "65") (name "DGND") (class "Default")
      (node (ref "C56") (pin "2") (pinfunction "2_2") (pintype "passive"))
      (node (ref "C57") (pin "2") (pinfunction "2_2") (pintype "passive"))
      (node (ref "C58") (pin "2") (pinfunction "2_2") (pintype "passive"))
      (node (ref "C59") (pin "2") (pinfunction "2_2") (pintype "passive"))
      (node (ref "C60") (pin "2") (pinfunction "2_2") (pintype "passive"))
      (node (ref "C61") (pin "2") (pinfunction "2_2") (pintype "passive"))
      (node (ref "C62") (pin "2") (pinfunction "2_2") (pintype "passive"))
      (node (ref "J3") (pin "G1") (pinfunction "G1_G1") (pintype "passive"))
      (node (ref "J3") (pin "G2") (pinfunction "G2_G2") (pintype "passive"))
      (node (ref "J3") (pin "G3") (pinfunction "G3_G3") (pintype "passive"))
      (node (ref "J3") (pin "G4") (pinfunction "G4_G4") (pintype "passive"))
      (node (ref "J4") (pin "G1") (pinfunction "G1_G1") (pintype "passive"))
      (node (ref "J4") (pin "G2") (pinfunction "G2_G2") (pintype "passive"))
      (node (ref "J4") (pin "G3") (pinfunction "G3_G3") (pintype "passive"))
      (node (ref "J4") (pin "G4") (pinfunction "G4_G4") (pintype "passive"))
      (node (ref "U11") (pin "17") (pinfunction "DGND_17") (pintype "power_in"))
      (node (ref "U11") (pin "24") (pinfunction "DGND_24") (pintype "power_in"))
      (node (ref "U11") (pin "7") (pinfunction "DGND_7") (pintype "power_in"))
      (node (ref "U11") (pin "74") (pinfunction "DGND_74") (pintype "power_in"))
      (node (ref "U11") (pin "84") (pinfunction "DGND_84") (pintype "power_in"))
    )
    (net (code "66") (name "Net-(U11-DAC_BP)") (class "Default")
      (node (ref "C93") (pin "1") (pinfunction "1_1") (pintype "passive"))
      (node (ref "C94") (pin "1") (pinfunction "1_1") (pintype "passive"))
      (node (ref "C95") (pin "1") (pinfunction "1_1") (pintype "passive"))
      (node (ref "C96") (pin "1") (pinfunction "1_1") (pintype "passive"))
      (node (ref "U11") (pin "45") (pinfunction "DAC_BP_45") (pintype "input"))
    )
    (net (code "67") (name "Net-(U11-DAC_RSET)") (class "Default")
      (node (ref "R42") (pin "2") (pinfunction "2_2") (pintype "passive"))
      (node (ref "U11") (pin "48") (pinfunction "DAC_RSET_48") (pintype "output"))
    )
    (net (code "68") (name "Net-(U11-LOOP_FILTER)") (class "Default")
      (node (ref "C85") (pin "2") (pinfunction "2_2") (pintype "passive"))
      (node (ref "C86") (pin "2") (pinfunction "2_2") (pintype "passive"))
      (node (ref "U11") (pin "58") (pinfunction "LOOP_FILTER_58") (pintype "output"))
    )
    (net (code "69") (name "Net-(U11-REF)") (class "Default")
      (node (ref "C85") (pin "1") (pinfunction "1_1") (pintype "passive"))
      (node (ref "C86") (pin "1") (pinfunction "1_1") (pintype "passive"))
      (node (ref "C87") (pin "1") (pinfunction "1_1") (pintype "passive"))
      (node (ref "C88") (pin "1") (pinfunction "1_1") (pintype "passive"))
      (node (ref "U11") (pin "59") (pinfunction "REF_59") (pintype "output"))
    )
    (net (code "70") (name "Net-(U13-D)") (class "Default")
      (node (ref "C97") (pin "1") (pinfunction "1_1") (pintype "passive"))
      (node (ref "C98") (pin "1") (pinfunction "1_1") (pintype "passive"))
      (node (ref "U13") (pin "1") (pinfunction "D_1") (pintype "input"))
      (node (ref "U13") (pin "15") (pinfunction "VREF_15") (pintype "output"))
      (node (ref "U13") (pin "16") (pinfunction "VT_16") (pintype "passive"))
    )
    (net (code "71") (name "Net-(U13-Q)") (class "Default")
      (node (ref "C89") (pin "1") (pinfunction "1_1") (pintype "passive"))
      (node (ref "R39") (pin "1") (pinfunction "1_1") (pintype "passive"))
      (node (ref "U13") (pin "12") (pinfunction "Q_12") (pintype "output"))
    )
    (net (code "72") (name "Net-(U13-~{D})") (class "Default")
      (node (ref "C90") (pin "2") (pinfunction "2_2") (pintype "passive"))
      (node (ref "U13") (pin "2") (pinfunction "~{D}_2") (pintype "input"))
    )
    (net (code "73") (name "Net-(U13-~{Q})") (class "Default")
      (node (ref "C91") (pin "1") (pinfunction "1_1") (pintype "passive"))
      (node (ref "R41") (pin "2") (pinfunction "2_2") (pintype "passive"))
      (node (ref "U13") (pin "11") (pinfunction "~{Q}_11") (pintype "output"))
    )
    (net (code "74") (name "Net-(U14-RFOUT)") (class "Default")
      (node (ref "C90") (pin "1") (pinfunction "1_1") (pintype "passive"))
      (node (ref "U14") (pin "10") (pinfunction "RFOUT_10") (pintype "output"))
    )
    (net (code "75") (name "VCO_VCC") (class "Default")
      (node (ref "C84") (pin "1") (pinfunction "1_1") (pintype "passive"))
      (node (ref "U14") (pin "14") (pinfunction "VCC_14") (pintype "power_in"))
    )
    (net (code "76") (name "unconnected-(J3-Pad13)") (class "Default")
      (node (ref "J3") (pin "13") (pinfunction "13_13") (pintype "passive"))
    )
    (net (code "77") (name "unconnected-(J3-Pad15)") (class "Default")
      (node (ref "J3") (pin "15") (pinfunction "15_15") (pintype "passive"))
    )
    (net (code "78") (name "unconnected-(J3-Pad17)") (class "Default")
      (node (ref "J3") (pin "17") (pinfunction "17_17") (pintype "passive"))
    )
    (net (code "79") (name "unconnected-(J3-Pad19)") (class "Default")
      (node (ref "J3") (pin "19") (pinfunction "19_19") (pintype "passive"))
    )
    (net (code "80") (name "unconnected-(J3-Pad21)") (class "Default")
      (node (ref "J3") (pin "21") (pinfunction "21_21") (pintype "passive"))
    )
    (net (code "81") (name "unconnected-(J3-Pad22)") (class "Default")
      (node (ref "J3") (pin "22") (pinfunction "22_22") (pintype "passive"))
    )
    (net (code "82") (name "unconnected-(J3-Pad23)") (class "Default")
      (node (ref "J3") (pin "23") (pinfunction "23_23") (pintype "passive"))
    )
    (net (code "83") (name "unconnected-(J3-Pad24)") (class "Default")
      (node (ref "J3") (pin "24") (pinfunction "24_24") (pintype "passive"))
    )
    (net (code "84") (name "unconnected-(J3-Pad25)") (class "Default")
      (node (ref "J3") (pin "25") (pinfunction "25_25") (pintype "passive"))
    )
    (net (code "85") (name "unconnected-(J3-Pad26)") (class "Default")
      (node (ref "J3") (pin "26") (pinfunction "26_26") (pintype "passive"))
    )
    (net (code "86") (name "unconnected-(J3-Pad27)") (class "Default")
      (node (ref "J3") (pin "27") (pinfunction "27_27") (pintype "passive"))
    )
    (net (code "87") (name "unconnected-(J3-Pad28)") (class "Default")
      (node (ref "J3") (pin "28") (pinfunction "28_28") (pintype "passive"))
    )
    (net (code "88") (name "unconnected-(J3-Pad29)") (class "Default")
      (node (ref "J3") (pin "29") (pinfunction "29_29") (pintype "passive"))
    )
    (net (code "89") (name "unconnected-(J3-Pad30)") (class "Default")
      (node (ref "J3") (pin "30") (pinfunction "30_30") (pintype "passive"))
    )
    (net (code "90") (name "unconnected-(J3-Pad31)") (class "Default")
      (node (ref "J3") (pin "31") (pinfunction "31_31") (pintype "passive"))
    )
    (net (code "91") (name "unconnected-(J3-Pad32)") (class "Default")
      (node (ref "J3") (pin "32") (pinfunction "32_32") (pintype "passive"))
    )
    (net (code "92") (name "unconnected-(J3-Pad33)") (class "Default")
      (node (ref "J3") (pin "33") (pinfunction "33_33") (pintype "passive"))
    )
    (net (code "93") (name "unconnected-(J3-Pad34)") (class "Default")
      (node (ref "J3") (pin "34") (pinfunction "34_34") (pintype "passive"))
    )
    (net (code "94") (name "unconnected-(J3-Pad35)") (class "Default")
      (node (ref "J3") (pin "35") (pinfunction "35_35") (pintype "passive"))
    )
    (net (code "95") (name "unconnected-(J3-Pad36)") (class "Default")
      (node (ref "J3") (pin "36") (pinfunction "36_36") (pintype "passive"))
    )
    (net (code "96") (name "unconnected-(J3-Pad37)") (class "Default")
      (node (ref "J3") (pin "37") (pinfunction "37_37") (pintype "passive"))
    )
    (net (code "97") (name "unconnected-(J3-Pad38)") (class "Default")
      (node (ref "J3") (pin "38") (pinfunction "38_38") (pintype "passive"))
    )
    (net (code "98") (name "unconnected-(J3-Pad39)") (class "Default")
      (node (ref "J3") (pin "39") (pinfunction "39_39") (pintype "passive"))
    )
    (net (code "99") (name "unconnected-(J3-Pad40)") (class "Default")
      (node (ref "J3") (pin "40") (pinfunction "40_40") (pintype "passive"))
    )
    (net (code "100") (name "unconnected-(J4-Pad33)") (class "Default")
      (node (ref "J4") (pin "33") (pinfunction "33_33") (pintype "passive"))
    )
    (net (code "101") (name "unconnected-(J4-Pad34)") (class "Default")
      (node (ref "J4") (pin "34") (pinfunction "34_34") (pintype "passive"))
    )
    (net (code "102") (name "unconnected-(J4-Pad35)") (class "Default")
      (node (ref "J4") (pin "35") (pinfunction "35_35") (pintype "passive"))
    )
    (net (code "103") (name "unconnected-(J4-Pad36)") (class "Default")
      (node (ref "J4") (pin "36") (pinfunction "36_36") (pintype "passive"))
    )
    (net (code "104") (name "unconnected-(J4-Pad37)") (class "Default")
      (node (ref "J4") (pin "37") (pinfunction "37_37") (pintype "passive"))
    )
    (net (code "105") (name "unconnected-(J4-Pad38)") (class "Default")
      (node (ref "J4") (pin "38") (pinfunction "38_38") (pintype "passive"))
    )
    (net (code "106") (name "unconnected-(J4-Pad39)") (class "Default")
      (node (ref "J4") (pin "39") (pinfunction "39_39") (pintype "passive"))
    )
    (net (code "107") (name "unconnected-(J4-Pad40)") (class "Default")
      (node (ref "J4") (pin "40") (pinfunction "40_40") (pintype "passive"))
    )
    (net (code "108") (name "unconnected-(U11-SYNC_IN-Pad62)") (class "Default")
      (node (ref "U11") (pin "62") (pinfunction "SYNC_IN_62") (pintype "input"))
    )
    (net (code "109") (name "unconnected-(U11-SYNC_OUT-Pad61)") (class "Default")
      (node (ref "U11") (pin "61") (pinfunction "SYNC_OUT_61") (pintype "output"))
    )
    (net (code "110") (name "unconnected-(U13-NC-Pad3)") (class "Default")
      (node (ref "U13") (pin "3") (pinfunction "NC_3") (pintype "passive+no_connect"))
    )
    (net (code "111") (name "unconnected-(U13-NC-Pad4)") (class "Default")
      (node (ref "U13") (pin "4") (pinfunction "NC_4") (pintype "passive+no_connect"))
    )
    (net (code "112") (name "unconnected-(U13-NC-Pad5)") (class "Default")
      (node (ref "U13") (pin "5") (pinfunction "NC_5") (pintype "passive+no_connect"))
    )
    (net (code "113") (name "unconnected-(U13-NC-Pad6)") (class "Default")
      (node (ref "U13") (pin "6") (pinfunction "NC_6") (pintype "passive+no_connect"))
    )
    (net (code "114") (name "unconnected-(U13-NC-Pad9)") (class "Default")
      (node (ref "U13") (pin "9") (pinfunction "NC_9") (pintype "passive+no_connect"))
    )
    (net (code "115") (name "unconnected-(U13-NC-Pad10)") (class "Default")
      (node (ref "U13") (pin "10") (pinfunction "NC_10") (pintype "passive+no_connect"))
    )
  )
)
